# CapteurHumidite.net
KiCad netlist of a schematic drawn in EAGLE
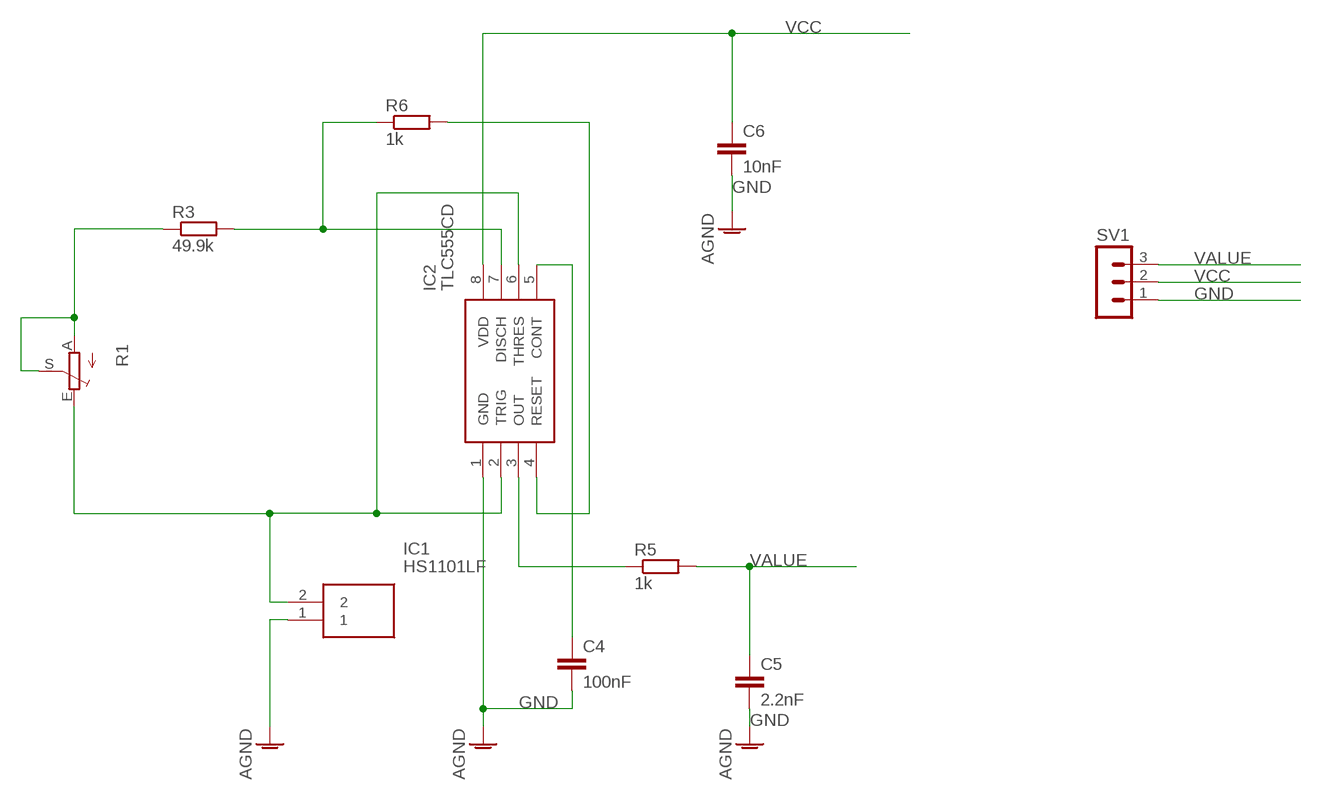
[diagram p0: schematic, sheet 1]

(export (version "E")
  (design (tool "Eeschema 10.0.6"))
  (components
    (comp (ref "C4")
      (value "100nF")
      (footprint "eagle-import:C0603")
      (libsource (lib "eagle-import") (part "C-EUC0603"))
    )
    (comp (ref "C5")
      (value "2.2nF")
      (footprint "eagle-import:C0603")
      (libsource (lib "eagle-import") (part "C-EUC0603"))
    )
    (comp (ref "C6")
      (value "10nF")
      (footprint "eagle-import:C0603")
      (libsource (lib "eagle-import") (part "C-EUC0603"))
    )
    (comp (ref "IC1")
      (value "HS1101LF")
      (footprint "eagle-import:HS1101LF")
      (fields (field (name "MOUSER_PART_NUMBER") "824-HS1101LF"))
      (libsource (lib "eagle-import") (part "HS1101LF"))
    )
    (comp (ref "IC2")
      (value "TLC555CD")
      (footprint "eagle-import:SOIC127P600X175-8N")
      (fields (field (name "MOUSER_PART_NUMBER") "595-TLC555CD"))
      (libsource (lib "eagle-import") (part "TLC555CD"))
    )
    (comp (ref "R1")
      (value "TRIM_EU-B25P")
      (footprint "eagle-import:B25P")
      (libsource (lib "eagle-import") (part "TRIM_EU-B25P"))
    )
    (comp (ref "R3")
      (value "49.9k")
      (footprint "eagle-import:R0603")
      (libsource (lib "eagle-import") (part "R-EU_R0603"))
    )
    (comp (ref "R5")
      (value "1k")
      (footprint "eagle-import:R0603")
      (libsource (lib "eagle-import") (part "R-EU_R0603"))
    )
    (comp (ref "R6")
      (value "1k")
      (footprint "eagle-import:R0603")
      (libsource (lib "eagle-import") (part "R-EU_R0603"))
    )
    (comp (ref "SV1")
      (value "MA03-1")
      (footprint "eagle-import:MA03-1")
      (libsource (lib "eagle-import") (part "MA03-1"))
    )
  )
  (nets
    (net (code "1") (name "/VALUE") (class "Default")
      (node (ref "C5") (pin "1") (pinfunction "1_1") (pintype "passive"))
      (node (ref "R5") (pin "2") (pinfunction "2_2") (pintype "passive"))
      (node (ref "SV1") (pin "3") (pinfunction "3_3") (pintype "passive"))
    )
    (net (code "2") (name "/VCC") (class "Default")
      (node (ref "C6") (pin "1") (pinfunction "1_1") (pintype "passive"))
      (node (ref "IC2") (pin "8") (pinfunction "VDD_8") (pintype "bidirectional"))
      (node (ref "SV1") (pin "2") (pinfunction "2_2") (pintype "passive"))
    )
    (net (code "3") (name "AGND") (class "Default")
      (node (ref "C4") (pin "2") (pinfunction "2_2") (pintype "passive"))
      (node (ref "C5") (pin "2") (pinfunction "2_2") (pintype "passive"))
      (node (ref "C6") (pin "2") (pinfunction "2_2") (pintype "passive"))
      (node (ref "IC1") (pin "1") (pinfunction "1_1") (pintype "bidirectional"))
      (node (ref "IC2") (pin "1") (pinfunction "GND_1") (pintype "bidirectional"))
      (node (ref "SV1") (pin "1") (pinfunction "1_1") (pintype "passive"))
    )
    (net (code "4") (name "Net-(IC2-CONT)") (class "Default")
      (node (ref "C4") (pin "1") (pinfunction "1_1") (pintype "passive"))
      (node (ref "IC2") (pin "5") (pinfunction "CONT_5") (pintype "bidirectional"))
    )
    (net (code "5") (name "Net-(IC2-DISCH)") (class "Default")
      (node (ref "IC2") (pin "7") (pinfunction "DISCH_7") (pintype "bidirectional"))
      (node (ref "R3") (pin "2") (pinfunction "2_2") (pintype "passive"))
      (node (ref "R6") (pin "1") (pinfunction "1_1") (pintype "passive"))
    )
    (net (code "6") (name "Net-(IC2-OUT)") (class "Default")
      (node (ref "IC2") (pin "3") (pinfunction "OUT_3") (pintype "bidirectional"))
      (node (ref "R5") (pin "1") (pinfunction "1_1") (pintype "passive"))
    )
    (net (code "7") (name "Net-(IC2-RESET)") (class "Default")
      (node (ref "IC2") (pin "4") (pinfunction "RESET_4") (pintype "bidirectional"))
      (node (ref "R6") (pin "2") (pinfunction "2_2") (pintype "passive"))
    )
    (net (code "8") (name "Net-(IC2-THRES)") (class "Default")
      (node (ref "IC1") (pin "2") (pinfunction "2_2") (pintype "bidirectional"))
      (node (ref "IC2") (pin "2") (pinfunction "TRIG_2") (pintype "bidirectional"))
      (node (ref "IC2") (pin "6") (pinfunction "THRES_6") (pintype "bidirectional"))
      (node (ref "R1") (pin "E") (pinfunction "E_E") (pintype "passive"))
    )
    (net (code "9") (name "Net-(R1-PadA)") (class "Default")
      (node (ref "R1") (pin "A") (pinfunction "A_A") (pintype "passive"))
      (node (ref "R1") (pin "S") (pinfunction "S_S") (pintype "passive"))
      (node (ref "R3") (pin "1") (pinfunction "1_1") (pintype "passive"))
    )
  )
)
